# Python_stm32f4_V1_0_0.net
KiCad netlist of a schematic drawn in Altium Designer
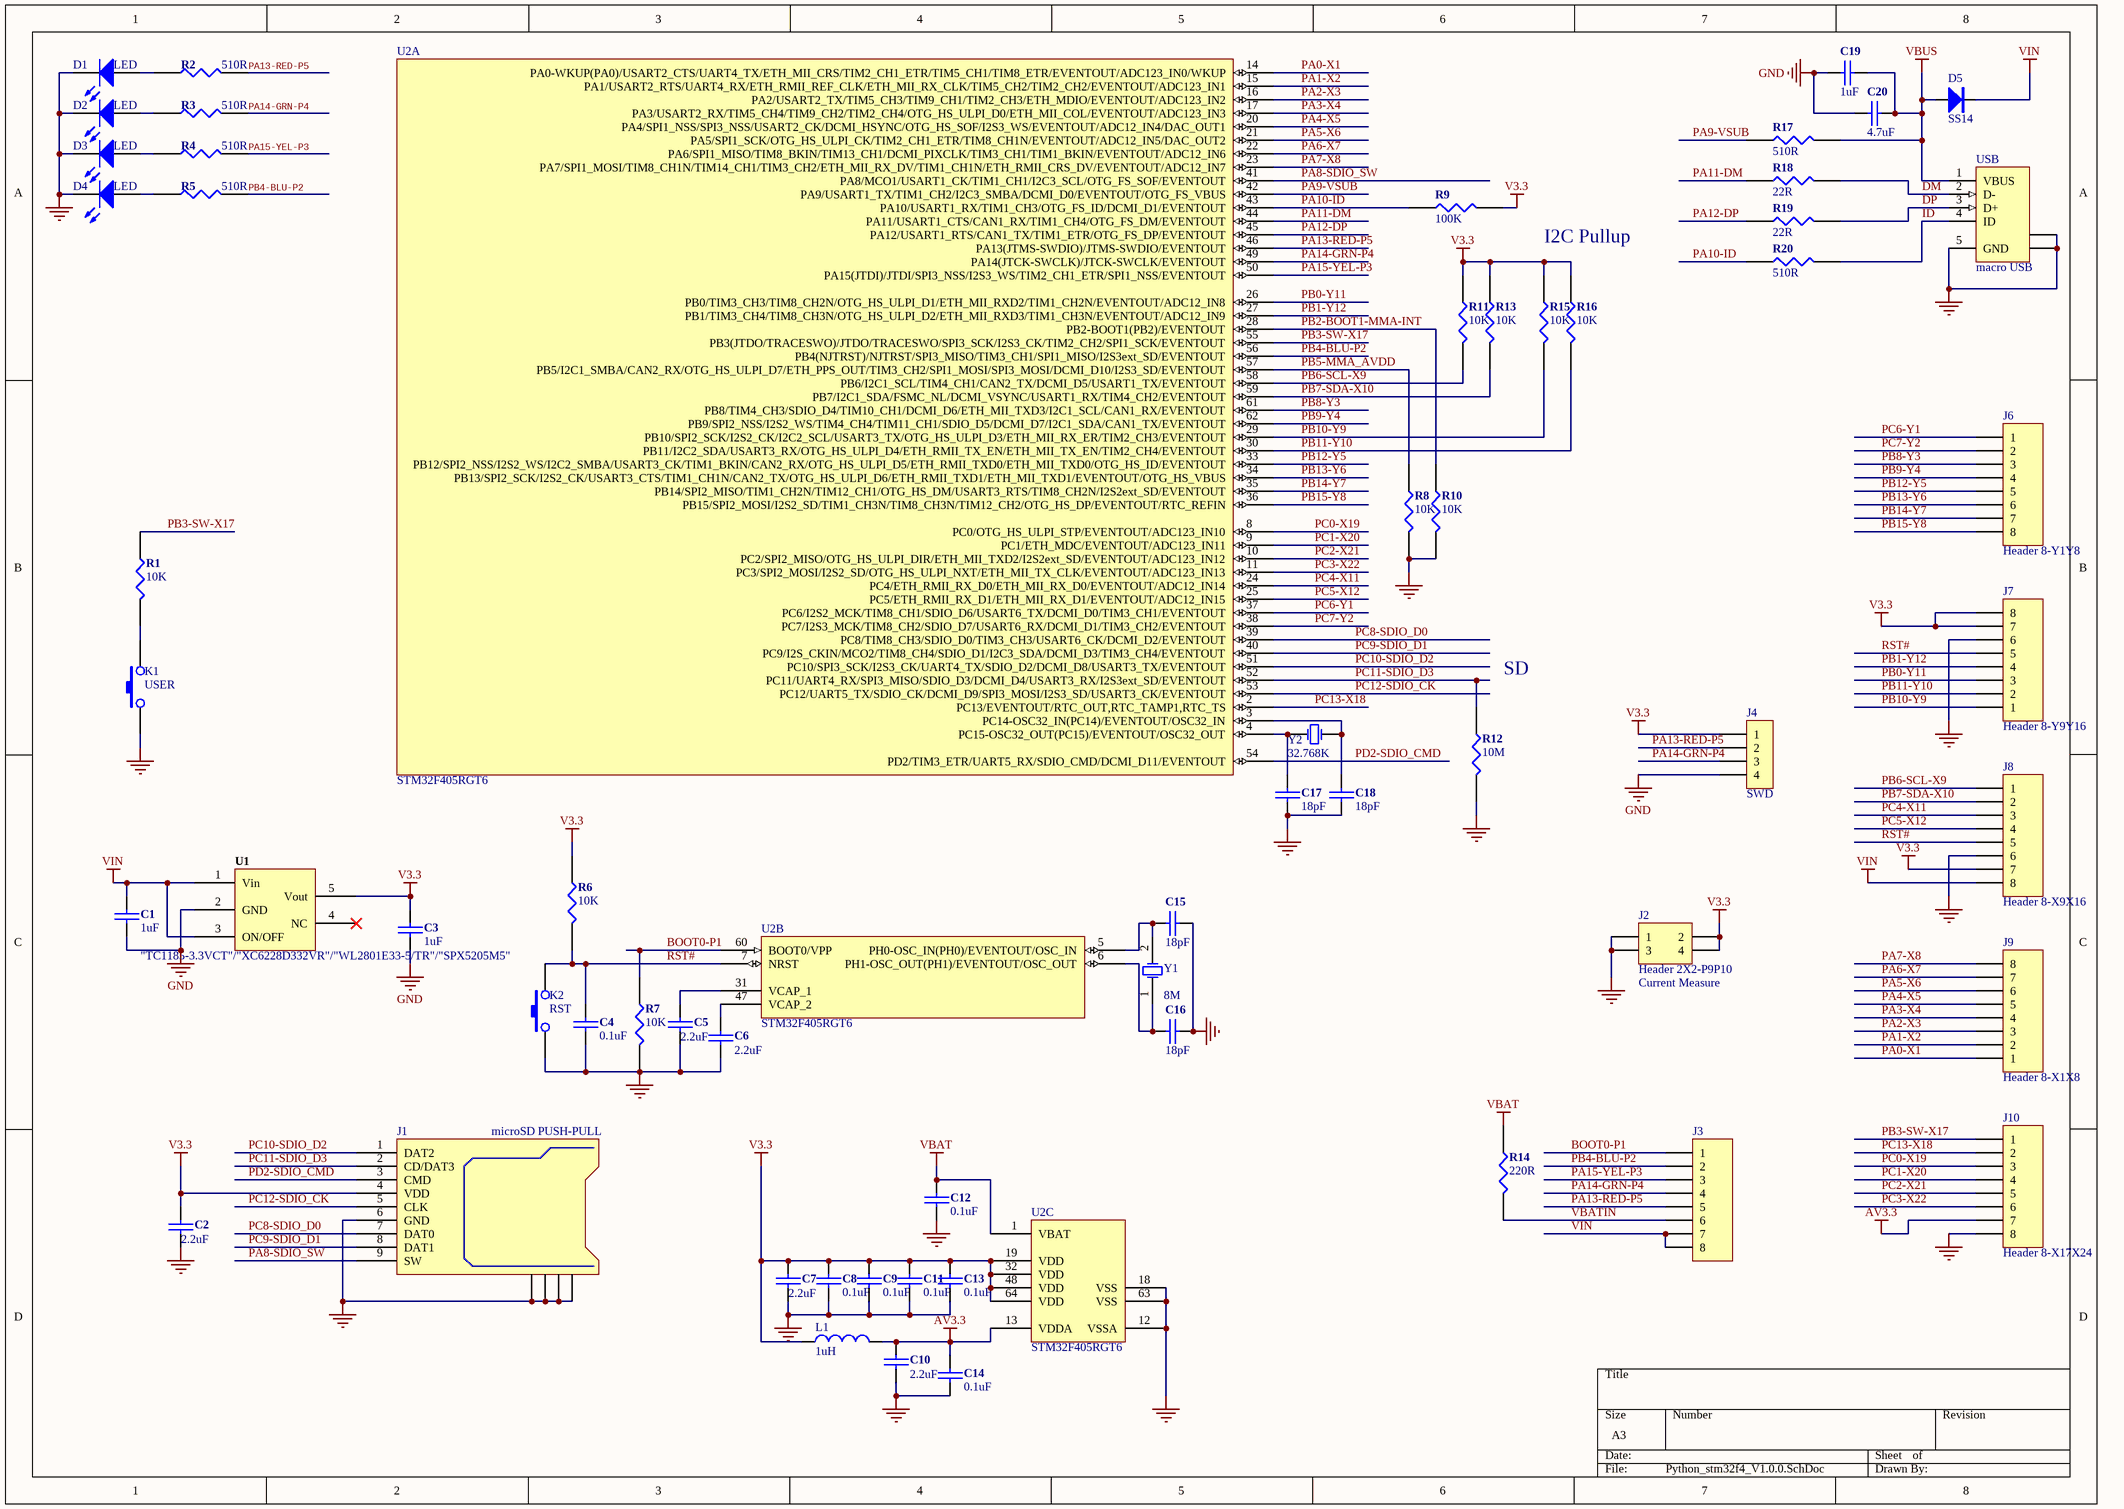
[diagram p0: Python_stm32f4_V1.0.0.SchDoc]

(export (version "E")
  (design (tool "Eeschema 10.0.6"))
  (components
    (comp (ref "C1") (value "1uF") (footprint "C0402") (libsource (lib "*") (part "电容")))
    (comp (ref "C2")
      (value "2.2uF")
      (footprint "C0402")
      (description "SMT电容")
      (libsource (lib "MyLibrarySum") (part "CAP"))
    )
    (comp (ref "C3") (value "1uF") (footprint "C0402") (libsource (lib "*") (part "电容")))
    (comp (ref "C4") (value "0.1uF") (footprint "C0402") (libsource (lib "*") (part "电容")))
    (comp (ref "C5")
      (value "2.2uF")
      (footprint "C0402")
      (description "SMT电容")
      (libsource (lib "MyLibrarySum") (part "CAP"))
    )
    (comp (ref "C6")
      (value "2.2uF")
      (footprint "C0402")
      (description "SMT电容")
      (libsource (lib "MyLibrarySum") (part "CAP"))
    )
    (comp (ref "C7")
      (value "2.2uF")
      (footprint "C0402")
      (description "SMT电容")
      (libsource (lib "MyLibrarySum") (part "CAP"))
    )
    (comp (ref "C8") (value "0.1uF") (footprint "C0402") (libsource (lib "*") (part "电容")))
    (comp (ref "C9") (value "0.1uF") (footprint "C0402") (libsource (lib "*") (part "电容")))
    (comp (ref "C10")
      (value "2.2uF")
      (footprint "C0402")
      (description "SMT电容")
      (libsource (lib "MyLibrarySum") (part "CAP"))
    )
    (comp (ref "C11") (value "0.1uF") (footprint "C0402") (libsource (lib "*") (part "电容")))
    (comp (ref "C12") (value "0.1uF") (footprint "C0402") (libsource (lib "*") (part "电容")))
    (comp (ref "C13") (value "0.1uF") (footprint "C0402") (libsource (lib "*") (part "电容")))
    (comp (ref "C14") (value "0.1uF") (footprint "C0402") (libsource (lib "*") (part "电容")))
    (comp (ref "C15")
      (value "18pF")
      (footprint "C0402")
      (description "SMT电容")
      (libsource (lib "MyLibrarySum") (part "CAP"))
    )
    (comp (ref "C16")
      (value "18pF")
      (footprint "C0402")
      (description "SMT电容")
      (libsource (lib "MyLibrarySum") (part "CAP"))
    )
    (comp (ref "C17")
      (value "18pF")
      (footprint "C0402")
      (description "SMT电容")
      (libsource (lib "MyLibrarySum") (part "CAP"))
    )
    (comp (ref "C18")
      (value "18pF")
      (footprint "C0402")
      (description "SMT电容")
      (libsource (lib "MyLibrarySum") (part "CAP"))
    )
    (comp (ref "C19") (value "1uF") (footprint "C0402") (libsource (lib "*") (part "电容")))
    (comp (ref "C20")
      (value "4.7uF")
      (footprint "C0402")
      (description "SMT电容")
      (libsource (lib "*") (part "CAP"))
    )
    (comp (ref "D1")
      (value "LED")
      (footprint "LED0603-green")
      (description "Typical INFRARED GaAs LED")
      (fields (field (name "PUBLISHER") "Altium Limited"))
      (libsource (lib "Miscellaneous Devices") (part "LED0"))
    )
    (comp (ref "D2")
      (value "LED")
      (footprint "LED0603-green")
      (description "Typical INFRARED GaAs LED")
      (fields (field (name "PUBLISHER") "Altium Limited"))
      (libsource (lib "Miscellaneous Devices") (part "LED0"))
    )
    (comp (ref "D3")
      (value "LED")
      (footprint "LED0603-green")
      (description "Typical INFRARED GaAs LED")
      (fields (field (name "PUBLISHER") "Altium Limited"))
      (libsource (lib "Miscellaneous Devices") (part "LED0"))
    )
    (comp (ref "D4")
      (value "LED")
      (footprint "LED0603-green")
      (description "Typical INFRARED GaAs LED")
      (fields (field (name "PUBLISHER") "Altium Limited"))
      (libsource (lib "Miscellaneous Devices") (part "LED0"))
    )
    (comp (ref "D5") (value "SS14") (footprint "Diode-0603") (libsource (lib "s_device") (part "Diode")))
    (comp (ref "J1")
      (value "microSD PUSH-PULL")
      (footprint "MICROSD-1")
      (libsource (lib "s_device") (part "microSD PUSH-PULL"))
    )
    (comp (ref "J2")
      (value "Header 2X2-P9P10")
      (footprint "HDR2X2")
      (description "Header, 2-Pin, Dual row")
      (fields (field (name "PUBLISHER") "Altium Limited"))
      (libsource (lib "Miscellaneous Connectors") (part "Header 2X2"))
    )
    (comp (ref "J3")
      (value "~")
      (footprint "HEADER-8")
      (description "Header, 8-Pin")
      (fields (field (name "PUBLISHER") "Altium Limited"))
      (libsource (lib "Miscellaneous Connectors") (part "Header 8"))
    )
    (comp (ref "J4")
      (value "SWD")
      (footprint "HEADER-4")
      (description "Connector")
      (libsource (lib "MyLibrarySum") (part "CON4"))
    )
    (comp (ref "J6")
      (value "Header 8-Y1Y8")
      (footprint "HEADER-8")
      (description "Header, 8-Pin")
      (fields (field (name "PUBLISHER") "Altium Limited"))
      (libsource (lib "Miscellaneous Connectors") (part "Header 8"))
    )
    (comp (ref "J7")
      (value "Header 8-Y9Y16")
      (footprint "HEADER-8")
      (description "Header, 8-Pin")
      (fields (field (name "PUBLISHER") "Altium Limited"))
      (libsource (lib "") (part "Header 8_1"))
    )
    (comp (ref "J8")
      (value "Header 8-X9X16")
      (footprint "HEADER-8")
      (description "Header, 8-Pin")
      (fields (field (name "PUBLISHER") "Altium Limited"))
      (libsource (lib "Miscellaneous Connectors") (part "Header 8"))
    )
    (comp (ref "J9")
      (value "Header 8-X1X8")
      (footprint "HEADER-8")
      (description "Header, 8-Pin")
      (fields (field (name "PUBLISHER") "Altium Limited"))
      (libsource (lib "") (part "Header 8_1"))
    )
    (comp (ref "J10")
      (value "Header 8-X17X24")
      (footprint "HEADER-8")
      (description "Header, 8-Pin")
      (fields (field (name "PUBLISHER") "Altium Limited"))
      (libsource (lib "Miscellaneous Connectors") (part "Header 8"))
    )
    (comp (ref "K1")
      (value "USER")
      (footprint "SW-4PIN-DIP")
      (description "轻触按键")
      (libsource (lib "MyLibrarySum") (part "SW-PB-1"))
    )
    (comp (ref "K2")
      (value "RST")
      (footprint "SW-4PIN-DIP")
      (description "轻触按键")
      (libsource (lib "MyLibrarySum") (part "SW-PB-1"))
    )
    (comp (ref "L1")
      (value "1uH")
      (footprint "C0402")
      (description "Inductor")
      (fields (field (name "PUBLISHER") "Altium Limited"))
      (libsource (lib "MyLibrarySum") (part "Inductor"))
    )
    (comp (ref "R1")
      (value "10K")
      (footprint "R0402 -1")
      (description "SMT电阻")
      (libsource (lib "*") (part "RES1"))
    )
    (comp (ref "R2")
      (value "510R")
      (footprint "R0402 -1")
      (description "SMT电阻")
      (libsource (lib "*") (part "RES1"))
    )
    (comp (ref "R3")
      (value "510R")
      (footprint "R0402 -1")
      (description "SMT电阻")
      (libsource (lib "*") (part "RES1"))
    )
    (comp (ref "R4")
      (value "510R")
      (footprint "R0402 -1")
      (description "SMT电阻")
      (libsource (lib "*") (part "RES1"))
    )
    (comp (ref "R5")
      (value "510R")
      (footprint "R0402 -1")
      (description "SMT电阻")
      (libsource (lib "*") (part "RES1"))
    )
    (comp (ref "R6")
      (value "10K")
      (footprint "R0402 -1")
      (description "SMT电阻")
      (libsource (lib "*") (part "RES1"))
    )
    (comp (ref "R7")
      (value "10K")
      (footprint "R0402 -1")
      (description "SMT电阻")
      (libsource (lib "*") (part "RES1"))
    )
    (comp (ref "R8")
      (value "10K")
      (footprint "R0402 -1")
      (description "SMT电阻")
      (libsource (lib "*") (part "RES1"))
    )
    (comp (ref "R9")
      (value "100K")
      (footprint "R0402 -1")
      (description "SMT电阻")
      (libsource (lib "*") (part "RES1"))
    )
    (comp (ref "R10")
      (value "10K")
      (footprint "R0402 -1")
      (description "SMT电阻")
      (libsource (lib "*") (part "RES1"))
    )
    (comp (ref "R11")
      (value "10K")
      (footprint "R0402 -1")
      (description "SMT电阻")
      (libsource (lib "*") (part "RES1"))
    )
    (comp (ref "R12")
      (value "10M")
      (footprint "R0402 -1")
      (description "SMT电阻")
      (libsource (lib "*") (part "RES1"))
    )
    (comp (ref "R13")
      (value "10K")
      (footprint "R0402 -1")
      (description "SMT电阻")
      (libsource (lib "*") (part "RES1"))
    )
    (comp (ref "R14")
      (value "220R")
      (footprint "R0402 -1")
      (description "SMT电阻")
      (libsource (lib "*") (part "RES1"))
    )
    (comp (ref "R15")
      (value "10K")
      (footprint "R0402 -1")
      (description "SMT电阻")
      (libsource (lib "*") (part "RES1"))
    )
    (comp (ref "R16")
      (value "10K")
      (footprint "R0402 -1")
      (description "SMT电阻")
      (libsource (lib "*") (part "RES1"))
    )
    (comp (ref "R17")
      (value "510R")
      (footprint "R0402 -1")
      (description "SMT电阻")
      (libsource (lib "*") (part "RES1"))
    )
    (comp (ref "R18")
      (value "22R")
      (footprint "R0402 -1")
      (description "SMT电阻")
      (libsource (lib "*") (part "RES1"))
    )
    (comp (ref "R19")
      (value "22R")
      (footprint "R0402 -1")
      (description "SMT电阻")
      (libsource (lib "*") (part "RES1"))
    )
    (comp (ref "R20")
      (value "510R")
      (footprint "R0402 -1")
      (description "SMT电阻")
      (libsource (lib "*") (part "RES1"))
    )
    (comp (ref "U1")
      (value "\"TC1185-3.3VCT\"/\"XC6228D332VR\"/\"WL2801E33-5/TR\"/\"SPX5205M5\"")
      (footprint "SOT-23-5")
      (description "LDO")
      (libsource (lib "*") (part "S1132"))
    )
    (comp (ref "U2")
      (value "STM32F405RGT6")
      (footprint "LQFP-64")
      (libsource (lib "s_mcu") (part "STM32F405RGT6"))
    )
    (comp (ref "USB")
      (value "macro USB")
      (footprint "MICRO_USB_9")
      (description "USB 2.0, Right Angle, SMT, B Type, Receptacle, 5 Position, Black")
      (fields (field (name "PUBLISHER") "Altium Limited"))
      (libsource (lib "s_connect") (part "macro USB"))
    )
    (comp (ref "Y1")
      (value "XTAL")
      (footprint "XTAL")
      (description "Crystal Oscillator")
      (fields (field (name "ALTIUM_UNNAMED_1") "8M") (field (name "PUBLISHER") "Altium Limited"))
      (libsource (lib "MyLibrarySum") (part "XTAL"))
    )
    (comp (ref "Y2") (value "32.768K") (footprint "HDR1X2") (libsource (lib "s_crystal") (part "XTAL")))
  )
  (nets
    (net (code "1") (name "/BOOT0-P1") (class "Default")
      (node (ref "J3") (pin "1") (pinfunction "1_1") (pintype "passive"))
      (node (ref "R7") (pin "1") (pinfunction "1_1") (pintype "passive"))
      (node (ref "U2") (pin "60") (pinfunction "BOOT0/VPP_60") (pintype "input"))
    )
    (net (code "2") (name "/DM") (class "Default")
      (node (ref "R18") (pin "2") (pinfunction "2_2") (pintype "passive"))
      (node (ref "USB") (pin "2") (pinfunction "D-_2") (pintype "input"))
    )
    (net (code "3") (name "/DP") (class "Default")
      (node (ref "R19") (pin "2") (pinfunction "2_2") (pintype "passive"))
      (node (ref "USB") (pin "3") (pinfunction "D+_3") (pintype "input"))
    )
    (net (code "4") (name "/ID") (class "Default")
      (node (ref "R20") (pin "2") (pinfunction "2_2") (pintype "passive"))
      (node (ref "USB") (pin "4") (pinfunction "ID_4") (pintype "power_in"))
    )
    (net (code "5") (name "/PA0-X1") (class "Default")
      (node (ref "J9") (pin "1") (pinfunction "1_1") (pintype "passive"))
      (node (ref "U2") (pin "14") (pinfunction "PA0-WKUP(PA0)/USART2_CTS/UART4_TX/ETH_MII_CRS/TIM2_CH1_ETR/TIM5_CH1/TIM8_ETR/EVENTOUT/ADC123_IN0/WKUP_14") (pintype "bidirectional"))
    )
    (net (code "6") (name "/PA1-X2") (class "Default")
      (node (ref "J9") (pin "2") (pinfunction "2_2") (pintype "passive"))
      (node (ref "U2") (pin "15") (pinfunction "PA1/USART2_RTS/UART4_RX/ETH_RMII_REF_CLK/ETH_MII_RX_CLK/TIM5_CH2/TIM2_CH2/EVENTOUT/ADC123_IN1_15") (pintype "bidirectional"))
    )
    (net (code "7") (name "/PA2-X3") (class "Default")
      (node (ref "J9") (pin "3") (pinfunction "3_3") (pintype "passive"))
      (node (ref "U2") (pin "16") (pinfunction "PA2/USART2_TX/TIM5_CH3/TIM9_CH1/TIM2_CH3/ETH_MDIO/EVENTOUT/ADC123_IN2_16") (pintype "bidirectional"))
    )
    (net (code "8") (name "/PA3-X4") (class "Default")
      (node (ref "J9") (pin "4") (pinfunction "4_4") (pintype "passive"))
      (node (ref "U2") (pin "17") (pinfunction "PA3/USART2_RX/TIM5_CH4/TIM9_CH2/TIM2_CH4/OTG_HS_ULPI_D0/ETH_MII_COL/EVENTOUT/ADC123_IN3_17") (pintype "bidirectional"))
    )
    (net (code "9") (name "/PA4-X5") (class "Default")
      (node (ref "J9") (pin "5") (pinfunction "5_5") (pintype "passive"))
      (node (ref "U2") (pin "20") (pinfunction "PA4/SPI1_NSS/SPI3_NSS/USART2_CK/DCMI_HSYNC/OTG_HS_SOF/I2S3_WS/EVENTOUT/ADC12_IN4/DAC_OUT1_20") (pintype "bidirectional"))
    )
    (net (code "10") (name "/PA5-X6") (class "Default")
      (node (ref "J9") (pin "6") (pinfunction "6_6") (pintype "passive"))
      (node (ref "U2") (pin "21") (pinfunction "PA5/SPI1_SCK/OTG_HS_ULPI_CK/TIM2_CH1_ETR/TIM8_CH1N/EVENTOUT/ADC12_IN5/DAC_OUT2_21") (pintype "bidirectional"))
    )
    (net (code "11") (name "/PA6-X7") (class "Default")
      (node (ref "J9") (pin "7") (pinfunction "7_7") (pintype "passive"))
      (node (ref "U2") (pin "22") (pinfunction "PA6/SPI1_MISO/TIM8_BKIN/TIM13_CH1/DCMI_PIXCLK/TIM3_CH1/TIM1_BKIN/EVENTOUT/ADC12_IN6_22") (pintype "bidirectional"))
    )
    (net (code "12") (name "/PA7-X8") (class "Default")
      (node (ref "J9") (pin "8") (pinfunction "8_8") (pintype "passive"))
      (node (ref "U2") (pin "23") (pinfunction "PA7/SPI1_MOSI/TIM8_CH1N/TIM14_CH1/TIM3_CH2/ETH_MII_RX_DV/TIM1_CH1N/ETH_RMII_CRS_DV/EVENTOUT/ADC12_IN7_23") (pintype "bidirectional"))
    )
    (net (code "13") (name "/PA8-SDIO_SW") (class "Default")
      (node (ref "J1") (pin "9") (pinfunction "SW_9") (pintype "passive"))
      (node (ref "U2") (pin "41") (pinfunction "PA8/MCO1/USART1_CK/TIM1_CH1/I2C3_SCL/OTG_FS_SOF/EVENTOUT_41") (pintype "bidirectional"))
    )
    (net (code "14") (name "/PA9-VSUB") (class "Default")
      (node (ref "R17") (pin "1") (pinfunction "1_1") (pintype "passive"))
      (node (ref "U2") (pin "42") (pinfunction "PA9/USART1_TX/TIM1_CH2/I2C3_SMBA/DCMI_D0/EVENTOUT/OTG_FS_VBUS_42") (pintype "bidirectional"))
    )
    (net (code "15") (name "/PA10-ID") (class "Default")
      (node (ref "R20") (pin "1") (pinfunction "1_1") (pintype "passive"))
      (node (ref "R9") (pin "1") (pinfunction "1_1") (pintype "passive"))
      (node (ref "U2") (pin "43") (pinfunction "PA10/USART1_RX/TIM1_CH3/OTG_FS_ID/DCMI_D1/EVENTOUT_43") (pintype "bidirectional"))
    )
    (net (code "16") (name "/PA11-DM") (class "Default")
      (node (ref "R18") (pin "1") (pinfunction "1_1") (pintype "passive"))
      (node (ref "U2") (pin "44") (pinfunction "PA11/USART1_CTS/CAN1_RX/TIM1_CH4/OTG_FS_DM/EVENTOUT_44") (pintype "bidirectional"))
    )
    (net (code "17") (name "/PA12-DP") (class "Default")
      (node (ref "R19") (pin "1") (pinfunction "1_1") (pintype "passive"))
      (node (ref "U2") (pin "45") (pinfunction "PA12/USART1_RTS/CAN1_TX/TIM1_ETR/OTG_FS_DP/EVENTOUT_45") (pintype "bidirectional"))
    )
    (net (code "18") (name "/PA13-RED-P5") (class "Default")
      (node (ref "J3") (pin "5") (pinfunction "5_5") (pintype "passive"))
      (node (ref "J4") (pin "2") (pinfunction "2_2") (pintype "passive"))
      (node (ref "R2") (pin "2") (pinfunction "2_2") (pintype "passive"))
      (node (ref "U2") (pin "46") (pinfunction "PA13(JTMS-SWDIO)/JTMS-SWDIO/EVENTOUT_46") (pintype "bidirectional"))
    )
    (net (code "19") (name "/PA14-GRN-P4") (class "Default")
      (node (ref "J3") (pin "4") (pinfunction "4_4") (pintype "passive"))
      (node (ref "J4") (pin "3") (pinfunction "3_3") (pintype "passive"))
      (node (ref "R3") (pin "2") (pinfunction "2_2") (pintype "passive"))
      (node (ref "U2") (pin "49") (pinfunction "PA14(JTCK-SWCLK)/JTCK-SWCLK/EVENTOUT_49") (pintype "bidirectional"))
    )
    (net (code "20") (name "/PA15-YEL-P3") (class "Default")
      (node (ref "J3") (pin "3") (pinfunction "3_3") (pintype "passive"))
      (node (ref "R4") (pin "2") (pinfunction "2_2") (pintype "passive"))
      (node (ref "U2") (pin "50") (pinfunction "PA15(JTDI)/JTDI/SPI3_NSS/I2S3_WS/TIM2_CH1_ETR/SPI1_NSS/EVENTOUT_50") (pintype "bidirectional"))
    )
    (net (code "21") (name "/PB0-Y11") (class "Default")
      (node (ref "J7") (pin "3") (pinfunction "3_3") (pintype "passive"))
      (node (ref "U2") (pin "26") (pinfunction "PB0/TIM3_CH3/TIM8_CH2N/OTG_HS_ULPI_D1/ETH_MII_RXD2/TIM1_CH2N/EVENTOUT/ADC12_IN8_26") (pintype "bidirectional"))
    )
    (net (code "22") (name "/PB1-Y12") (class "Default")
      (node (ref "J7") (pin "4") (pinfunction "4_4") (pintype "passive"))
      (node (ref "U2") (pin "27") (pinfunction "PB1/TIM3_CH4/TIM8_CH3N/OTG_HS_ULPI_D2/ETH_MII_RXD3/TIM1_CH3N/EVENTOUT/ADC12_IN9_27") (pintype "bidirectional"))
    )
    (net (code "23") (name "/PB2-BOOT1-MMA-INT") (class "Default")
      (node (ref "R10") (pin "1") (pinfunction "1_1") (pintype "passive"))
      (node (ref "U2") (pin "28") (pinfunction "PB2-BOOT1(PB2)/EVENTOUT_28") (pintype "bidirectional"))
    )
    (net (code "24") (name "/PB3-SW-X17") (class "Default")
      (node (ref "J10") (pin "1") (pinfunction "1_1") (pintype "passive"))
      (node (ref "R1") (pin "1") (pinfunction "1_1") (pintype "passive"))
      (node (ref "U2") (pin "55") (pinfunction "PB3(JTDO/TRACESWO)/JTDO/TRACESWO/SPI3_SCK/I2S3_CK/TIM2_CH2/SPI1_SCK/EVENTOUT_55") (pintype "bidirectional"))
    )
    (net (code "25") (name "/PB4-BLU-P2") (class "Default")
      (node (ref "J3") (pin "2") (pinfunction "2_2") (pintype "passive"))
      (node (ref "R5") (pin "2") (pinfunction "2_2") (pintype "passive"))
      (node (ref "U2") (pin "56") (pinfunction "PB4(NJTRST)/NJTRST/SPI3_MISO/TIM3_CH1/SPI1_MISO/I2S3ext_SD/EVENTOUT_56") (pintype "bidirectional"))
    )
    (net (code "26") (name "/PB5-MMA_AVDD") (class "Default")
      (node (ref "R8") (pin "1") (pinfunction "1_1") (pintype "passive"))
      (node (ref "U2") (pin "57") (pinfunction "PB5/I2C1_SMBA/CAN2_RX/OTG_HS_ULPI_D7/ETH_PPS_OUT/TIM3_CH2/SPI1_MOSI/SPI3_MOSI/DCMI_D10/I2S3_SD/EVENTOUT_57") (pintype "bidirectional"))
    )
    (net (code "27") (name "/PB6-SCL-X9") (class "Default")
      (node (ref "J8") (pin "1") (pinfunction "1_1") (pintype "passive"))
      (node (ref "R11") (pin "2") (pinfunction "2_2") (pintype "passive"))
      (node (ref "U2") (pin "58") (pinfunction "PB6/I2C1_SCL/TIM4_CH1/CAN2_TX/DCMI_D5/USART1_TX/EVENTOUT_58") (pintype "bidirectional"))
    )
    (net (code "28") (name "/PB7-SDA-X10") (class "Default")
      (node (ref "J8") (pin "2") (pinfunction "2_2") (pintype "passive"))
      (node (ref "R13") (pin "2") (pinfunction "2_2") (pintype "passive"))
      (node (ref "U2") (pin "59") (pinfunction "PB7/I2C1_SDA/FSMC_NL/DCMI_VSYNC/USART1_RX/TIM4_CH2/EVENTOUT_59") (pintype "bidirectional"))
    )
    (net (code "29") (name "/PB8-Y3") (class "Default")
      (node (ref "J6") (pin "3") (pinfunction "3_3") (pintype "passive"))
      (node (ref "U2") (pin "61") (pinfunction "PB8/TIM4_CH3/SDIO_D4/TIM10_CH1/DCMI_D6/ETH_MII_TXD3/I2C1_SCL/CAN1_RX/EVENTOUT_61") (pintype "bidirectional"))
    )
    (net (code "30") (name "/PB9-Y4") (class "Default")
      (node (ref "J6") (pin "4") (pinfunction "4_4") (pintype "passive"))
      (node (ref "U2") (pin "62") (pinfunction "PB9/SPI2_NSS/I2S2_WS/TIM4_CH4/TIM11_CH1/SDIO_D5/DCMI_D7/I2C1_SDA/CAN1_TX/EVENTOUT_62") (pintype "bidirectional"))
    )
    (net (code "31") (name "/PB10-Y9") (class "Default")
      (node (ref "J7") (pin "1") (pinfunction "1_1") (pintype "passive"))
      (node (ref "R15") (pin "2") (pinfunction "2_2") (pintype "passive"))
      (node (ref "U2") (pin "29") (pinfunction "PB10/SPI2_SCK/I2S2_CK/I2C2_SCL/USART3_TX/OTG_HS_ULPI_D3/ETH_MII_RX_ER/TIM2_CH3/EVENTOUT_29") (pintype "bidirectional"))
    )
    (net (code "32") (name "/PB11-Y10") (class "Default")
      (node (ref "J7") (pin "2") (pinfunction "2_2") (pintype "passive"))
      (node (ref "R16") (pin "2") (pinfunction "2_2") (pintype "passive"))
      (node (ref "U2") (pin "30") (pinfunction "PB11/I2C2_SDA/USART3_RX/OTG_HS_ULPI_D4/ETH_RMII_TX_EN/ETH_MII_TX_EN/TIM2_CH4/EVENTOUT_30") (pintype "bidirectional"))
    )
    (net (code "33") (name "/PB12-Y5") (class "Default")
      (node (ref "J6") (pin "5") (pinfunction "5_5") (pintype "passive"))
      (node (ref "U2") (pin "33") (pinfunction "PB12/SPI2_NSS/I2S2_WS/I2C2_SMBA/USART3_CK/TIM1_BKIN/CAN2_RX/OTG_HS_ULPI_D5/ETH_RMII_TXD0/ETH_MII_TXD0/OTG_HS_ID/EVENTOUT_33") (pintype "bidirectional"))
    )
    (net (code "34") (name "/PB13-Y6") (class "Default")
      (node (ref "J6") (pin "6") (pinfunction "6_6") (pintype "passive"))
      (node (ref "U2") (pin "34") (pinfunction "PB13/SPI2_SCK/I2S2_CK/USART3_CTS/TIM1_CH1N/CAN2_TX/OTG_HS_ULPI_D6/ETH_RMII_TXD1/ETH_MII_TXD1/EVENTOUT/OTG_HS_VBUS_34") (pintype "bidirectional"))
    )
    (net (code "35") (name "/PB14-Y7") (class "Default")
      (node (ref "J6") (pin "7") (pinfunction "7_7") (pintype "passive"))
      (node (ref "U2") (pin "35") (pinfunction "PB14/SPI2_MISO/TIM1_CH2N/TIM12_CH1/OTG_HS_DM/USART3_RTS/TIM8_CH2N/I2S2ext_SD/EVENTOUT_35") (pintype "bidirectional"))
    )
    (net (code "36") (name "/PB15-Y8") (class "Default")
      (node (ref "J6") (pin "8") (pinfunction "8_8") (pintype "passive"))
      (node (ref "U2") (pin "36") (pinfunction "PB15/SPI2_MOSI/I2S2_SD/TIM1_CH3N/TIM8_CH3N/TIM12_CH2/OTG_HS_DP/EVENTOUT/RTC_REFIN_36") (pintype "bidirectional"))
    )
    (net (code "37") (name "/PC0-X19") (class "Default")
      (node (ref "J10") (pin "3") (pinfunction "3_3") (pintype "passive"))
      (node (ref "U2") (pin "8") (pinfunction "PC0/OTG_HS_ULPI_STP/EVENTOUT/ADC123_IN10_8") (pintype "bidirectional"))
    )
    (net (code "38") (name "/PC1-X20") (class "Default")
      (node (ref "J10") (pin "4") (pinfunction "4_4") (pintype "passive"))
      (node (ref "U2") (pin "9") (pinfunction "PC1/ETH_MDC/EVENTOUT/ADC123_IN11_9") (pintype "bidirectional"))
    )
    (net (code "39") (name "/PC2-X21") (class "Default")
      (node (ref "J10") (pin "5") (pinfunction "5_5") (pintype "passive"))
      (node (ref "U2") (pin "10") (pinfunction "PC2/SPI2_MISO/OTG_HS_ULPI_DIR/ETH_MII_TXD2/I2S2ext_SD/EVENTOUT/ADC123_IN12_10") (pintype "bidirectional"))
    )
    (net (code "40") (name "/PC3-X22") (class "Default")
      (node (ref "J10") (pin "6") (pinfunction "6_6") (pintype "passive"))
      (node (ref "U2") (pin "11") (pinfunction "PC3/SPI2_MOSI/I2S2_SD/OTG_HS_ULPI_NXT/ETH_MII_TX_CLK/EVENTOUT/ADC123_IN13_11") (pintype "bidirectional"))
    )
    (net (code "41") (name "/PC4-X11") (class "Default")
      (node (ref "J8") (pin "3") (pinfunction "3_3") (pintype "passive"))
      (node (ref "U2") (pin "24") (pinfunction "PC4/ETH_RMII_RX_D0/ETH_MII_RX_D0/EVENTOUT/ADC12_IN14_24") (pintype "bidirectional"))
    )
    (net (code "42") (name "/PC5-X12") (class "Default")
      (node (ref "J8") (pin "4") (pinfunction "4_4") (pintype "passive"))
      (node (ref "U2") (pin "25") (pinfunction "PC5/ETH_RMII_RX_D1/ETH_MII_RX_D1/EVENTOUT/ADC12_IN15_25") (pintype "bidirectional"))
    )
    (net (code "43") (name "/PC6-Y1") (class "Default")
      (node (ref "J6") (pin "1") (pinfunction "1_1") (pintype "passive"))
      (node (ref "U2") (pin "37") (pinfunction "PC6/I2S2_MCK/TIM8_CH1/SDIO_D6/USART6_TX/DCMI_D0/TIM3_CH1/EVENTOUT_37") (pintype "bidirectional"))
    )
    (net (code "44") (name "/PC7-Y2") (class "Default")
      (node (ref "J6") (pin "2") (pinfunction "2_2") (pintype "passive"))
      (node (ref "U2") (pin "38") (pinfunction "PC7/I2S3_MCK/TIM8_CH2/SDIO_D7/USART6_RX/DCMI_D1/TIM3_CH2/EVENTOUT_38") (pintype "bidirectional"))
    )
    (net (code "45") (name "/PC8-SDIO_D0") (class "Default")
      (node (ref "J1") (pin "7") (pinfunction "DAT0_7") (pintype "passive"))
      (node (ref "U2") (pin "39") (pinfunction "PC8/TIM8_CH3/SDIO_D0/TIM3_CH3/USART6_CK/DCMI_D2/EVENTOUT_39") (pintype "bidirectional"))
    )
    (net (code "46") (name "/PC9-SDIO_D1") (class "Default")
      (node (ref "J1") (pin "8") (pinfunction "DAT1_8") (pintype "passive"))
      (node (ref "U2") (pin "40") (pinfunction "PC9/I2S_CKIN/MCO2/TIM8_CH4/SDIO_D1/I2C3_SDA/DCMI_D3/TIM3_CH4/EVENTOUT_40") (pintype "bidirectional"))
    )
    (net (code "47") (name "/PC10-SDIO_D2") (class "Default")
      (node (ref "J1") (pin "1") (pinfunction "DAT2_1") (pintype "passive"))
      (node (ref "U2") (pin "51") (pinfunction "PC10/SPI3_SCK/I2S3_CK/UART4_TX/SDIO_D2/DCMI_D8/USART3_TX/EVENTOUT_51") (pintype "bidirectional"))
    )
    (net (code "48") (name "/PC11-SDIO_D3") (class "Default")
      (node (ref "J1") (pin "2") (pinfunction "CD/DAT3_2") (pintype "passive"))
      (node (ref "R12") (pin "1") (pinfunction "1_1") (pintype "passive"))
      (node (ref "U2") (pin "52") (pinfunction "PC11/UART4_RX/SPI3_MISO/SDIO_D3/DCMI_D4/USART3_RX/I2S3ext_SD/EVENTOUT_52") (pintype "bidirectional"))
    )
    (net (code "49") (name "/PC12-SDIO_CK") (class "Default")
      (node (ref "J1") (pin "5") (pinfunction "CLK_5") (pintype "passive"))
      (node (ref "U2") (pin "53") (pinfunction "PC12/UART5_TX/SDIO_CK/DCMI_D9/SPI3_MOSI/I2S3_SD/USART3_CK/EVENTOUT_53") (pintype "bidirectional"))
    )
    (net (code "50") (name "/PC13-X18") (class "Default")
      (node (ref "J10") (pin "2") (pinfunction "2_2") (pintype "passive"))
      (node (ref "U2") (pin "2") (pinfunction "PC13/EVENTOUT/RTC_OUT,RTC_TAMP1,RTC_TS_2") (pintype "bidirectional"))
    )
    (net (code "51") (name "/PD2-SDIO_CMD") (class "Default")
      (node (ref "J1") (pin "3") (pinfunction "CMD_3") (pintype "passive"))
      (node (ref "U2") (pin "54") (pinfunction "PD2/TIM3_ETR/UART5_RX/SDIO_CMD/DCMI_D11/EVENTOUT_54") (pintype "bidirectional"))
    )
    (net (code "52") (name "/RST#") (class "Default")
      (node (ref "C4") (pin "2") (pintype "passive"))
      (node (ref "J7") (pin "5") (pinfunction "5_5") (pintype "passive"))
      (node (ref "J8") (pin "5") (pinfunction "5_5") (pintype "passive"))
      (node (ref "K2") (pin "2") (pinfunction "2_2") (pintype "passive"))
      (node (ref "R6") (pin "2") (pinfunction "2_2") (pintype "passive"))
      (node (ref "U2") (pin "7") (pinfunction "NRST_7") (pintype "bidirectional"))
    )
    (net (code "53") (name "/VBATIN") (class "Default")
      (node (ref "J3") (pin "6") (pinfunction "6_6") (pintype "passive"))
      (node (ref "R14") (pin "2") (pinfunction "2_2") (pintype "passive"))
    )
    (net (code "54") (name "AV3.3") (class "Default")
      (node (ref "C10") (pin "1") (pinfunction "1_1") (pintype "passive"))
      (node (ref "C14") (pin "2") (pintype "passive"))
      (node (ref "J10") (pin "7") (pinfunction "7_7") (pintype "passive"))
      (node (ref "L1") (pin "2") (pinfunction "2_2") (pintype "passive"))
      (node (ref "U2") (pin "13") (pinfunction "VDDA_13") (pintype "power_in"))
    )
    (net (code "55") (name "GND") (class "Default")
      (node (ref "C1") (pin "1") (pintype "passive"))
      (node (ref "C10") (pin "2") (pinfunction "2_2") (pintype "passive"))
      (node (ref "C11") (pin "1") (pintype "passive"))
      (node (ref "C12") (pin "1") (pintype "passive"))
      (node (ref "C13") (pin "1") (pintype "passive"))
      (node (ref "C14") (pin "1") (pintype "passive"))
      (node (ref "C15") (pin "1") (pinfunction "1_1") (pintype "passive"))
      (node (ref "C16") (pin "1") (pinfunction "1_1") (pintype "passive"))
      (node (ref "C17") (pin "2") (pinfunction "2_2") (pintype "passive"))
      (node (ref "C18") (pin "2") (pinfunction "2_2") (pintype "passive"))
      (node (ref "C19") (pin "2") (pintype "passive"))
      (node (ref "C2") (pin "2") (pinfunction "2_2") (pintype "passive"))
      (node (ref "C20") (pin "2") (pinfunction "2_2") (pintype "passive"))
      (node (ref "C3") (pin "1") (pintype "passive"))
      (node (ref "C4") (pin "1") (pintype "passive"))
      (node (ref "C5") (pin "2") (pinfunction "2_2") (pintype "passive"))
      (node (ref "C6") (pin "2") (pinfunction "2_2") (pintype "passive"))
      (node (ref "C7") (pin "2") (pinfunction "2_2") (pintype "passive"))
      (node (ref "C8") (pin "1") (pintype "passive"))
      (node (ref "C9") (pin "1") (pintype "passive"))
      (node (ref "D1") (pin "2") (pinfunction "K_2") (pintype "passive"))
      (node (ref "D2") (pin "2") (pinfunction "K_2") (pintype "passive"))
      (node (ref "D3") (pin "2") (pinfunction "K_2") (pintype "passive"))
      (node (ref "D4") (pin "2") (pinfunction "K_2") (pintype "passive"))
      (node (ref "J1") (pin "6") (pinfunction "GND_6") (pintype "passive"))
      (node (ref "J1") (pin "GP1") (pintype "passive"))
      (node (ref "J1") (pin "GP2") (pintype "passive"))
      (node (ref "J1") (pin "GP3") (pintype "passive"))
      (node (ref "J1") (pin "GP4") (pintype "passive"))
      (node (ref "J10") (pin "8") (pinfunction "8_8") (pintype "passive"))
      (node (ref "J2") (pin "1") (pinfunction "1_1") (pintype "passive"))
      (node (ref "J2") (pin "3") (pinfunction "3_3") (pintype "passive"))
      (node (ref "J4") (pin "4") (pinfunction "4_4") (pintype "passive"))
      (node (ref "J7") (pin "6") (pinfunction "6_6") (pintype "passive"))
      (node (ref "J8") (pin "6") (pinfunction "6_6") (pintype "passive"))
      (node (ref "K1") (pin "1") (pinfunction "1_1") (pintype "passive"))
      (node (ref "K2") (pin "1") (pinfunction "1_1") (pintype "passive"))
      (node (ref "R10") (pin "2") (pinfunction "2_2") (pintype "passive"))
      (node (ref "R12") (pin "2") (pinfunction "2_2") (pintype "passive"))
      (node (ref "R7") (pin "2") (pinfunction "2_2") (pintype "passive"))
      (node (ref "R8") (pin "2") (pinfunction "2_2") (pintype "passive"))
      (node (ref "U1") (pin "2") (pinfunction "GND_2") (pintype "passive"))
      (node (ref "U2") (pin "12") (pinfunction "VSSA_12") (pintype "power_in"))
      (node (ref "U2") (pin "18") (pinfunction "VSS_18") (pintype "power_in"))
      (node (ref "U2") (pin "63") (pinfunction "VSS_63") (pintype "power_in"))
      (node (ref "USB") (pin "5") (pinfunction "GND_5") (pintype "passive"))
      (node (ref "USB") (pin "6") (pinfunction "SHLD_6") (pintype "passive"))
      (node (ref "USB") (pin "7") (pinfunction "SHLD_7") (pintype "passive"))
    )
    (net (code "56") (name "Net-(D1-A)") (class "Default")
      (node (ref "D1") (pin "1") (pinfunction "A_1") (pintype "passive"))
      (node (ref "R2") (pin "1") (pinfunction "1_1") (pintype "passive"))
    )
    (net (code "57") (name "Net-(D2-A)") (class "Default")
      (node (ref "D2") (pin "1") (pinfunction "A_1") (pintype "passive"))
      (node (ref "R3") (pin "1") (pinfunction "1_1") (pintype "passive"))
    )
    (net (code "58") (name "Net-(D3-A)") (class "Default")
      (node (ref "D3") (pin "1") (pinfunction "A_1") (pintype "passive"))
      (node (ref "R4") (pin "1") (pinfunction "1_1") (pintype "passive"))
    )
    (net (code "59") (name "Net-(D4-A)") (class "Default")
      (node (ref "D4") (pin "1") (pinfunction "A_1") (pintype "passive"))
      (node (ref "R5") (pin "1") (pinfunction "1_1") (pintype "passive"))
    )
    (net (code "60") (name "Net-(K1-Pad2)") (class "Default")
      (node (ref "K1") (pin "2") (pinfunction "2_2") (pintype "passive"))
      (node (ref "R1") (pin "2") (pinfunction "2_2") (pintype "passive"))
    )
    (net (code "61") (name "Net-(U2A-PC14-OSC32_IN(PC14){slash}EVENTOUT{slash}OSC32_IN)") (class "Default")
      (node (ref "C18") (pin "1") (pinfunction "1_1") (pintype "passive"))
      (node (ref "U2") (pin "3") (pinfunction "PC14-OSC32_IN(PC14)/EVENTOUT/OSC32_IN_3") (pintype "bidirectional"))
      (node (ref "Y2") (pin "2") (pinfunction "OSC2_2") (pintype "passive"))
    )
    (net (code "62") (name "Net-(U2A-PC15-OSC32_OUT(PC15){slash}EVENTOUT{slash}OSC32_OUT)") (class "Default")
      (node (ref "C17") (pin "1") (pinfunction "1_1") (pintype "passive"))
      (node (ref "U2") (pin "4") (pinfunction "PC15-OSC32_OUT(PC15)/EVENTOUT/OSC32_OUT_4") (pintype "bidirectional"))
      (node (ref "Y2") (pin "1") (pinfunction "OSC1_1") (pintype "passive"))
    )
    (net (code "63") (name "Net-(U2B-PH0-OSC_IN(PH0){slash}EVENTOUT{slash}OSC_IN)") (class "Default")
      (node (ref "C15") (pin "2") (pinfunction "2_2") (pintype "passive"))
      (node (ref "U2") (pin "5") (pinfunction "PH0-OSC_IN(PH0)/EVENTOUT/OSC_IN_5") (pintype "bidirectional"))
      (node (ref "Y1") (pin "2") (pinfunction "OSC2_2") (pintype "passive"))
    )
    (net (code "64") (name "Net-(U2B-PH1-OSC_OUT(PH1){slash}EVENTOUT{slash}OSC_OUT)") (class "Default")
      (node (ref "C16") (pin "2") (pinfunction "2_2") (pintype "passive"))
      (node (ref "U2") (pin "6") (pinfunction "PH1-OSC_OUT(PH1)/EVENTOUT/OSC_OUT_6") (pintype "bidirectional"))
      (node (ref "Y1") (pin "1") (pinfunction "OSC1_1") (pintype "passive"))
    )
    (net (code "65") (name "Net-(U2B-VCAP_1)") (class "Default")
      (node (ref "C5") (pin "1") (pinfunction "1_1") (pintype "passive"))
      (node (ref "U2") (pin "31") (pinfunction "VCAP_1_31") (pintype "power_in"))
    )
    (net (code "66") (name "Net-(U2B-VCAP_2)") (class "Default")
      (node (ref "C6") (pin "1") (pinfunction "1_1") (pintype "passive"))
      (node (ref "U2") (pin "47") (pinfunction "VCAP_2_47") (pintype "power_in"))
    )
    (net (code "67") (name "V3.3") (class "Default")
      (node (ref "C11") (pin "2") (pintype "passive"))
      (node (ref "C13") (pin "2") (pintype "passive"))
      (node (ref "C2") (pin "1") (pinfunction "1_1") (pintype "passive"))
      (node (ref "C3") (pin "2") (pintype "passive"))
      (node (ref "C7") (pin "1") (pinfunction "1_1") (pintype "passive"))
      (node (ref "C8") (pin "2") (pintype "passive"))
      (node (ref "C9") (pin "2") (pintype "passive"))
      (node (ref "J1") (pin "4") (pinfunction "VDD_4") (pintype "passive"))
      (node (ref "J2") (pin "2") (pinfunction "2_2") (pintype "passive"))
      (node (ref "J2") (pin "4") (pinfunction "4_4") (pintype "passive"))
      (node (ref "J4") (pin "1") (pinfunction "1_1") (pintype "passive"))
      (node (ref "J7") (pin "7") (pinfunction "7_7") (pintype "passive"))
      (node (ref "J7") (pin "8") (pinfunction "8_8") (pintype "passive"))
      (node (ref "J8") (pin "7") (pinfunction "7_7") (pintype "passive"))
      (node (ref "L1") (pin "1") (pinfunction "1_1") (pintype "passive"))
      (node (ref "R11") (pin "1") (pinfunction "1_1") (pintype "passive"))
      (node (ref "R13") (pin "1") (pinfunction "1_1") (pintype "passive"))
      (node (ref "R15") (pin "1") (pinfunction "1_1") (pintype "passive"))
      (node (ref "R16") (pin "1") (pinfunction "1_1") (pintype "passive"))
      (node (ref "R6") (pin "1") (pinfunction "1_1") (pintype "passive"))
      (node (ref "R9") (pin "2") (pinfunction "2_2") (pintype "passive"))
      (node (ref "U1") (pin "5") (pinfunction "Vout_5") (pintype "passive"))
      (node (ref "U2") (pin "19") (pinfunction "VDD_19") (pintype "power_in"))
      (node (ref "U2") (pin "32") (pinfunction "VDD_32") (pintype "power_in"))
      (node (ref "U2") (pin "48") (pinfunction "VDD_48") (pintype "power_in"))
      (node (ref "U2") (pin "64") (pinfunction "VDD_64") (pintype "power_in"))
    )
    (net (code "68") (name "VBAT") (class "Default")
      (node (ref "C12") (pin "2") (pintype "passive"))
      (node (ref "R14") (pin "1") (pinfunction "1_1") (pintype "passive"))
      (node (ref "U2") (pin "1") (pinfunction "VBAT_1") (pintype "power_in"))
    )
    (net (code "69") (name "VBUS") (class "Default")
      (node (ref "C19") (pin "1") (pintype "passive"))
      (node (ref "C20") (pin "1") (pinfunction "1_1") (pintype "passive"))
      (node (ref "D5") (pin "1") (pintype "passive"))
      (node (ref "R17") (pin "2") (pinfunction "2_2") (pintype "passive"))
      (node (ref "USB") (pin "1") (pinfunction "VBUS_1") (pintype "power_in"))
    )
    (net (code "70") (name "VIN") (class "Default")
      (node (ref "C1") (pin "2") (pintype "passive"))
      (node (ref "D5") (pin "2") (pintype "passive"))
      (node (ref "J3") (pin "7") (pinfunction "7_7") (pintype "passive"))
      (node (ref "J3") (pin "8") (pinfunction "8_8") (pintype "passive"))
      (node (ref "J8") (pin "8") (pinfunction "8_8") (pintype "passive"))
      (node (ref "U1") (pin "1") (pinfunction "Vin_1") (pintype "passive"))
      (node (ref "U1") (pin "3") (pinfunction "ON/OFF_3") (pintype "passive"))
    )
    (net (code "71") (name "unconnected-(U1-NC-Pad4)") (class "Default")
      (node (ref "U1") (pin "4") (pinfunction "NC_4") (pintype "passive+no_connect"))
    )
  )
)
